# SCH_Control_2024-03-25.net
KiCad netlist of a schematic drawn in EasyEDA
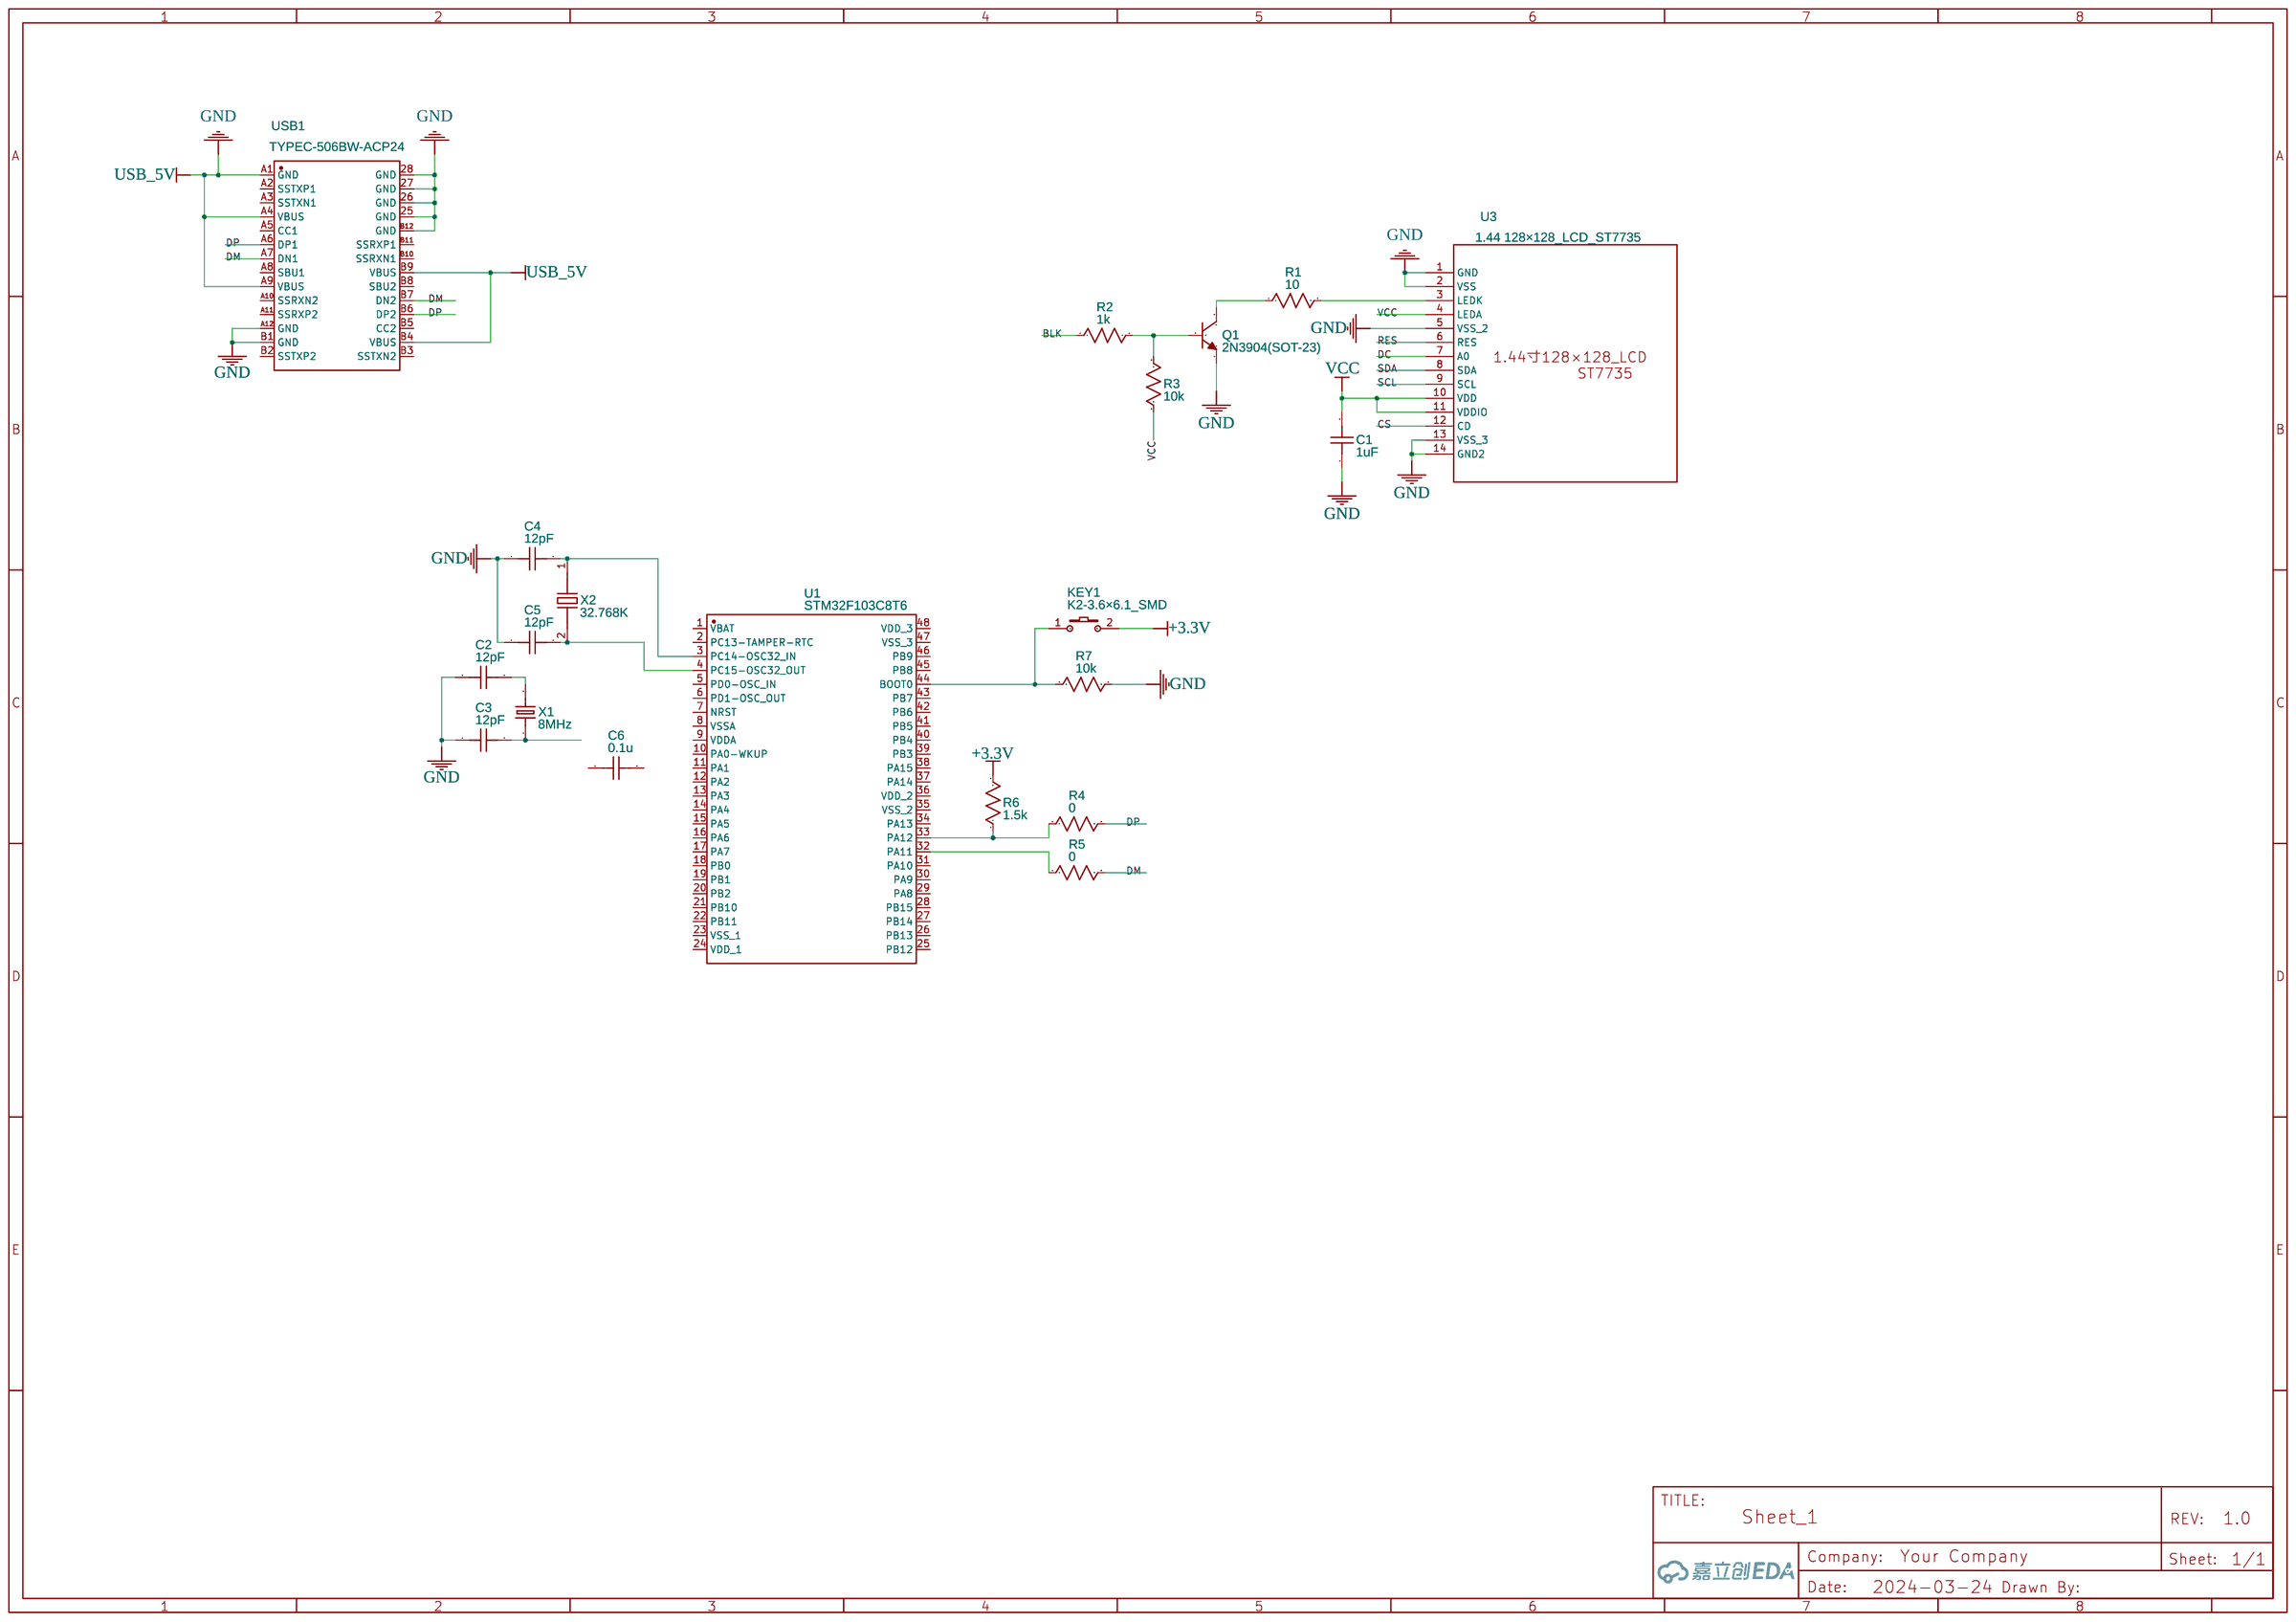
[diagram p0: schematic sheet]

(export (version "E")
  (design (tool "Eeschema 10.0.6"))
  (components
    (comp (ref "C1") (value "1uF") (libsource (lib "") (part "C_0603_US_1")))
    (comp (ref "C2") (value "12pF") (libsource (lib "") (part "C_0603_US")))
    (comp (ref "C3") (value "12pF") (libsource (lib "") (part "C_0603_US")))
    (comp (ref "C4") (value "12pF") (libsource (lib "") (part "C_0603_US")))
    (comp (ref "C5") (value "12pF") (libsource (lib "") (part "C_0603_US")))
    (comp (ref "C6") (value "0.1u") (libsource (lib "") (part "C_0603_US")))
    (comp (ref "KEY1")
      (value "K2-3.6×6.1_SMD")
      (fields (field (name "Manufacturer Part") "K2-1107ST-A4SW-06"))
      (libsource (lib "") (part "K2-3.6×6.1_SMD"))
    )
    (comp (ref "Q1")
      (value "2N3904(SOT-23)")
      (fields (field (name "Manufacturer Part") "2n3904S-RTK/PS") (field (name "Manufacturer") "KEC"))
      (libsource (lib "") (part "2N3904(SOT-23)"))
    )
    (comp (ref "R1") (value "10") (libsource (lib "") (part "R_0603_US")))
    (comp (ref "R2") (value "1k") (libsource (lib "") (part "R_0603_US")))
    (comp (ref "R3") (value "10k") (libsource (lib "") (part "R_0603_US_1")))
    (comp (ref "R4") (value "0") (libsource (lib "") (part "R_0603_US")))
    (comp (ref "R5") (value "0") (libsource (lib "") (part "R_0603_US")))
    (comp (ref "R6") (value "1.5k") (libsource (lib "") (part "R_0603_US_1")))
    (comp (ref "R7") (value "10k") (libsource (lib "") (part "R_0603_US")))
    (comp (ref "U1")
      (value "STM32F103C8T6")
      (fields (field (name "Manufacturer") "ST(意法半导体)"))
      (libsource (lib "") (part "STM32F103C8T6"))
    )
    (comp (ref "U3")
      (value "1.44 128×128_LCD_ST7735")
      (libsource (lib "") (part "1.44 128×128_LCD_ST7735【华迪短】"))
    )
    (comp (ref "USB1")
      (value "TYPEC-506BW-ACP24")
      (fields (field (name "Manufacturer") "XUNPU(讯普)"))
      (libsource (lib "") (part "TYPEC-506BW-ACP24"))
    )
    (comp (ref "X1")
      (value "8MHz")
      (fields
        (field (name "Manufacturer Part") "XJHCELNANF-8M")
        (field (name "Manufacturer") "TAITIEN(泰艺电子)")
      )
      (libsource (lib "") (part "XJHCCLNAND-8M"))
    )
    (comp (ref "X2")
      (value "32.768K")
      (fields (field (name "Manufacturer Part") "贴片晶振32.768k"))
      (libsource (lib "") (part "贴片晶振32.768K"))
    )
  )
  (nets
    (net (code "1") (name "+3.3V") (class "Default")
      (node (ref "KEY1") (pin "2") (pinfunction "2_2") (pintype "unspecified"))
      (node (ref "R6") (pin "2") (pinfunction "2_2") (pintype "unspecified"))
    )
    (net (code "2") (name "/BLK") (class "Default")
      (node (ref "R2") (pin "1") (pinfunction "1_1") (pintype "unspecified"))
    )
    (net (code "3") (name "/CS") (class "Default")
      (node (ref "U3") (pin "12") (pinfunction "CD_12") (pintype "unspecified"))
    )
    (net (code "4") (name "/DC") (class "Default")
      (node (ref "U3") (pin "7") (pinfunction "A0_7") (pintype "unspecified"))
    )
    (net (code "5") (name "/DM") (class "Default")
      (node (ref "R5") (pin "2") (pinfunction "2_2") (pintype "unspecified"))
      (node (ref "USB1") (pin "A7") (pinfunction "DN1_A7") (pintype "unspecified"))
      (node (ref "USB1") (pin "B7") (pinfunction "DN2_B7") (pintype "unspecified"))
    )
    (net (code "6") (name "/DP") (class "Default")
      (node (ref "R4") (pin "2") (pinfunction "2_2") (pintype "unspecified"))
      (node (ref "USB1") (pin "A6") (pinfunction "DP1_A6") (pintype "unspecified"))
      (node (ref "USB1") (pin "B6") (pinfunction "DP2_B6") (pintype "unspecified"))
    )
    (net (code "7") (name "/RES") (class "Default")
      (node (ref "U3") (pin "6") (pinfunction "RES_6") (pintype "unspecified"))
    )
    (net (code "8") (name "/SCL") (class "Default")
      (node (ref "U3") (pin "9") (pinfunction "SCL_9") (pintype "unspecified"))
    )
    (net (code "9") (name "/SDA") (class "Default")
      (node (ref "U3") (pin "8") (pinfunction "SDA_8") (pintype "unspecified"))
    )
    (net (code "10") (name "GND") (class "Default")
      (node (ref "C1") (pin "1") (pinfunction "1_1") (pintype "unspecified"))
      (node (ref "C2") (pin "1") (pinfunction "1_1") (pintype "unspecified"))
      (node (ref "C3") (pin "1") (pinfunction "1_1") (pintype "unspecified"))
      (node (ref "C4") (pin "1") (pinfunction "1_1") (pintype "unspecified"))
      (node (ref "C5") (pin "1") (pinfunction "1_1") (pintype "unspecified"))
      (node (ref "Q1") (pin "1") (pinfunction "E_1") (pintype "input"))
      (node (ref "R7") (pin "2") (pinfunction "2_2") (pintype "unspecified"))
      (node (ref "U3") (pin "1") (pinfunction "GND_1") (pintype "unspecified"))
      (node (ref "U3") (pin "13") (pinfunction "VSS_3_13") (pintype "unspecified"))
      (node (ref "U3") (pin "14") (pinfunction "GND2_14") (pintype "unspecified"))
      (node (ref "U3") (pin "2") (pinfunction "VSS_2") (pintype "unspecified"))
      (node (ref "U3") (pin "5") (pinfunction "VSS_2_5") (pintype "unspecified"))
      (node (ref "USB1") (pin "25") (pinfunction "GND_25") (pintype "unspecified"))
      (node (ref "USB1") (pin "26") (pinfunction "GND_26") (pintype "unspecified"))
      (node (ref "USB1") (pin "27") (pinfunction "GND_27") (pintype "unspecified"))
      (node (ref "USB1") (pin "28") (pinfunction "GND_28") (pintype "unspecified"))
      (node (ref "USB1") (pin "A1") (pinfunction "GND_A1") (pintype "unspecified"))
      (node (ref "USB1") (pin "A12") (pinfunction "GND_A12") (pintype "unspecified"))
      (node (ref "USB1") (pin "A4") (pinfunction "VBUS_A4") (pintype "unspecified"))
      (node (ref "USB1") (pin "A9") (pinfunction "VBUS_A9") (pintype "unspecified"))
      (node (ref "USB1") (pin "B1") (pinfunction "GND_B1") (pintype "unspecified"))
      (node (ref "USB1") (pin "B12") (pinfunction "GND_B12") (pintype "unspecified"))
      (node (ref "USB1") (pin "B4") (pinfunction "VBUS_B4") (pintype "unspecified"))
      (node (ref "USB1") (pin "B9") (pinfunction "VBUS_B9") (pintype "unspecified"))
    )
    (net (code "11") (name "Net-(C2-Pad2)") (class "Default")
      (node (ref "C2") (pin "2") (pinfunction "2_2") (pintype "unspecified"))
      (node (ref "X1") (pin "2") (pinfunction "2_2") (pintype "unspecified"))
    )
    (net (code "12") (name "Net-(C3-Pad2)") (class "Default")
      (node (ref "C3") (pin "2") (pinfunction "2_2") (pintype "unspecified"))
      (node (ref "X1") (pin "1") (pinfunction "1_1") (pintype "unspecified"))
    )
    (net (code "13") (name "Net-(Q1-B)") (class "Default")
      (node (ref "Q1") (pin "2") (pinfunction "B_2") (pintype "input"))
      (node (ref "R2") (pin "2") (pinfunction "2_2") (pintype "unspecified"))
      (node (ref "R3") (pin "2") (pinfunction "2_2") (pintype "unspecified"))
    )
    (net (code "14") (name "Net-(Q1-C)") (class "Default")
      (node (ref "Q1") (pin "3") (pinfunction "C_3") (pintype "input"))
      (node (ref "R1") (pin "1") (pinfunction "1_1") (pintype "unspecified"))
    )
    (net (code "15") (name "Net-(U1-BOOT0)") (class "Default")
      (node (ref "KEY1") (pin "1") (pinfunction "1_1") (pintype "unspecified"))
      (node (ref "R7") (pin "1") (pinfunction "1_1") (pintype "unspecified"))
      (node (ref "U1") (pin "44") (pinfunction "BOOT0_44") (pintype "unspecified"))
    )
    (net (code "16") (name "Net-(U1-PA11)") (class "Default")
      (node (ref "R5") (pin "1") (pinfunction "1_1") (pintype "unspecified"))
      (node (ref "U1") (pin "32") (pinfunction "PA11_32") (pintype "unspecified"))
    )
    (net (code "17") (name "Net-(U1-PA12)") (class "Default")
      (node (ref "R4") (pin "1") (pinfunction "1_1") (pintype "unspecified"))
      (node (ref "R6") (pin "1") (pinfunction "1_1") (pintype "unspecified"))
      (node (ref "U1") (pin "33") (pinfunction "PA12_33") (pintype "unspecified"))
    )
    (net (code "18") (name "Net-(U1-PC14-OSC32_IN)") (class "Default")
      (node (ref "C4") (pin "2") (pinfunction "2_2") (pintype "unspecified"))
      (node (ref "U1") (pin "3") (pinfunction "PC14-OSC32_IN_3") (pintype "unspecified"))
      (node (ref "X2") (pin "1") (pinfunction "1_1") (pintype "input"))
    )
    (net (code "19") (name "Net-(U1-PC15-OSC32_OUT)") (class "Default")
      (node (ref "C5") (pin "2") (pinfunction "2_2") (pintype "unspecified"))
      (node (ref "U1") (pin "4") (pinfunction "PC15-OSC32_OUT_4") (pintype "unspecified"))
      (node (ref "X2") (pin "2") (pinfunction "2_2") (pintype "input"))
    )
    (net (code "20") (name "Net-(U3-LEDK)") (class "Default")
      (node (ref "R1") (pin "2") (pinfunction "2_2") (pintype "unspecified"))
      (node (ref "U3") (pin "3") (pinfunction "LEDK_3") (pintype "unspecified"))
    )
    (net (code "21") (name "VCC") (class "Default")
      (node (ref "C1") (pin "2") (pinfunction "2_2") (pintype "unspecified"))
      (node (ref "R3") (pin "1") (pinfunction "1_1") (pintype "unspecified"))
      (node (ref "U3") (pin "10") (pinfunction "VDD_10") (pintype "unspecified"))
      (node (ref "U3") (pin "11") (pinfunction "VDDIO_11") (pintype "unspecified"))
      (node (ref "U3") (pin "4") (pinfunction "LEDA_4") (pintype "unspecified"))
    )
    (net (code "22") (name "unconnected-(C6-Pad1)") (class "Default")
      (node (ref "C6") (pin "1") (pinfunction "1_1") (pintype "unspecified"))
    )
    (net (code "23") (name "unconnected-(C6-Pad2)") (class "Default")
      (node (ref "C6") (pin "2") (pinfunction "2_2") (pintype "unspecified"))
    )
    (net (code "24") (name "unconnected-(U1-NRST-Pad7)") (class "Default")
      (node (ref "U1") (pin "7") (pinfunction "NRST_7") (pintype "unspecified"))
    )
    (net (code "25") (name "unconnected-(U1-PA0-WKUP-Pad10)") (class "Default")
      (node (ref "U1") (pin "10") (pinfunction "PA0-WKUP_10") (pintype "unspecified"))
    )
    (net (code "26") (name "unconnected-(U1-PA1-Pad11)") (class "Default")
      (node (ref "U1") (pin "11") (pinfunction "PA1_11") (pintype "unspecified"))
    )
    (net (code "27") (name "unconnected-(U1-PA2-Pad12)") (class "Default")
      (node (ref "U1") (pin "12") (pinfunction "PA2_12") (pintype "unspecified"))
    )
    (net (code "28") (name "unconnected-(U1-PA3-Pad13)") (class "Default")
      (node (ref "U1") (pin "13") (pinfunction "PA3_13") (pintype "unspecified"))
    )
    (net (code "29") (name "unconnected-(U1-PA4-Pad14)") (class "Default")
      (node (ref "U1") (pin "14") (pinfunction "PA4_14") (pintype "unspecified"))
    )
    (net (code "30") (name "unconnected-(U1-PA5-Pad15)") (class "Default")
      (node (ref "U1") (pin "15") (pinfunction "PA5_15") (pintype "unspecified"))
    )
    (net (code "31") (name "unconnected-(U1-PA6-Pad16)") (class "Default")
      (node (ref "U1") (pin "16") (pinfunction "PA6_16") (pintype "unspecified"))
    )
    (net (code "32") (name "unconnected-(U1-PA7-Pad17)") (class "Default")
      (node (ref "U1") (pin "17") (pinfunction "PA7_17") (pintype "unspecified"))
    )
    (net (code "33") (name "unconnected-(U1-PA8-Pad29)") (class "Default")
      (node (ref "U1") (pin "29") (pinfunction "PA8_29") (pintype "unspecified"))
    )
    (net (code "34") (name "unconnected-(U1-PA9-Pad30)") (class "Default")
      (node (ref "U1") (pin "30") (pinfunction "PA9_30") (pintype "unspecified"))
    )
    (net (code "35") (name "unconnected-(U1-PA10-Pad31)") (class "Default")
      (node (ref "U1") (pin "31") (pinfunction "PA10_31") (pintype "unspecified"))
    )
    (net (code "36") (name "unconnected-(U1-PA13-Pad34)") (class "Default")
      (node (ref "U1") (pin "34") (pinfunction "PA13_34") (pintype "unspecified"))
    )
    (net (code "37") (name "unconnected-(U1-PA14-Pad37)") (class "Default")
      (node (ref "U1") (pin "37") (pinfunction "PA14_37") (pintype "unspecified"))
    )
    (net (code "38") (name "unconnected-(U1-PA15-Pad38)") (class "Default")
      (node (ref "U1") (pin "38") (pinfunction "PA15_38") (pintype "unspecified"))
    )
    (net (code "39") (name "unconnected-(U1-PB0-Pad18)") (class "Default")
      (node (ref "U1") (pin "18") (pinfunction "PB0_18") (pintype "unspecified"))
    )
    (net (code "40") (name "unconnected-(U1-PB1-Pad19)") (class "Default")
      (node (ref "U1") (pin "19") (pinfunction "PB1_19") (pintype "unspecified"))
    )
    (net (code "41") (name "unconnected-(U1-PB2-Pad20)") (class "Default")
      (node (ref "U1") (pin "20") (pinfunction "PB2_20") (pintype "unspecified"))
    )
    (net (code "42") (name "unconnected-(U1-PB3-Pad39)") (class "Default")
      (node (ref "U1") (pin "39") (pinfunction "PB3_39") (pintype "unspecified"))
    )
    (net (code "43") (name "unconnected-(U1-PB4-Pad40)") (class "Default")
      (node (ref "U1") (pin "40") (pinfunction "PB4_40") (pintype "unspecified"))
    )
    (net (code "44") (name "unconnected-(U1-PB5-Pad41)") (class "Default")
      (node (ref "U1") (pin "41") (pinfunction "PB5_41") (pintype "unspecified"))
    )
    (net (code "45") (name "unconnected-(U1-PB6-Pad42)") (class "Default")
      (node (ref "U1") (pin "42") (pinfunction "PB6_42") (pintype "unspecified"))
    )
    (net (code "46") (name "unconnected-(U1-PB7-Pad43)") (class "Default")
      (node (ref "U1") (pin "43") (pinfunction "PB7_43") (pintype "unspecified"))
    )
    (net (code "47") (name "unconnected-(U1-PB8-Pad45)") (class "Default")
      (node (ref "U1") (pin "45") (pinfunction "PB8_45") (pintype "unspecified"))
    )
    (net (code "48") (name "unconnected-(U1-PB9-Pad46)") (class "Default")
      (node (ref "U1") (pin "46") (pinfunction "PB9_46") (pintype "unspecified"))
    )
    (net (code "49") (name "unconnected-(U1-PB10-Pad21)") (class "Default")
      (node (ref "U1") (pin "21") (pinfunction "PB10_21") (pintype "unspecified"))
    )
    (net (code "50") (name "unconnected-(U1-PB11-Pad22)") (class "Default")
      (node (ref "U1") (pin "22") (pinfunction "PB11_22") (pintype "unspecified"))
    )
    (net (code "51") (name "unconnected-(U1-PB12-Pad25)") (class "Default")
      (node (ref "U1") (pin "25") (pinfunction "PB12_25") (pintype "unspecified"))
    )
    (net (code "52") (name "unconnected-(U1-PB13-Pad26)") (class "Default")
      (node (ref "U1") (pin "26") (pinfunction "PB13_26") (pintype "unspecified"))
    )
    (net (code "53") (name "unconnected-(U1-PB14-Pad27)") (class "Default")
      (node (ref "U1") (pin "27") (pinfunction "PB14_27") (pintype "unspecified"))
    )
    (net (code "54") (name "unconnected-(U1-PB15-Pad28)") (class "Default")
      (node (ref "U1") (pin "28") (pinfunction "PB15_28") (pintype "unspecified"))
    )
    (net (code "55") (name "unconnected-(U1-PC13-TAMPER-RTC-Pad2)") (class "Default")
      (node (ref "U1") (pin "2") (pinfunction "PC13-TAMPER-RTC_2") (pintype "unspecified"))
    )
    (net (code "56") (name "unconnected-(U1-PD0-OSC_IN-Pad5)") (class "Default")
      (node (ref "U1") (pin "5") (pinfunction "PD0-OSC_IN_5") (pintype "unspecified"))
    )
    (net (code "57") (name "unconnected-(U1-PD1-OSC_OUT-Pad6)") (class "Default")
      (node (ref "U1") (pin "6") (pinfunction "PD1-OSC_OUT_6") (pintype "unspecified"))
    )
    (net (code "58") (name "unconnected-(U1-VBAT-Pad1)") (class "Default")
      (node (ref "U1") (pin "1") (pinfunction "VBAT_1") (pintype "unspecified"))
    )
    (net (code "59") (name "unconnected-(U1-VDDA-Pad9)") (class "Default")
      (node (ref "U1") (pin "9") (pinfunction "VDDA_9") (pintype "unspecified"))
    )
    (net (code "60") (name "unconnected-(U1-VDD_1-Pad24)") (class "Default")
      (node (ref "U1") (pin "24") (pinfunction "VDD_1_24") (pintype "unspecified"))
    )
    (net (code "61") (name "unconnected-(U1-VDD_2-Pad36)") (class "Default")
      (node (ref "U1") (pin "36") (pinfunction "VDD_2_36") (pintype "unspecified"))
    )
    (net (code "62") (name "unconnected-(U1-VDD_3-Pad48)") (class "Default")
      (node (ref "U1") (pin "48") (pinfunction "VDD_3_48") (pintype "unspecified"))
    )
    (net (code "63") (name "unconnected-(U1-VSSA-Pad8)") (class "Default")
      (node (ref "U1") (pin "8") (pinfunction "VSSA_8") (pintype "unspecified"))
    )
    (net (code "64") (name "unconnected-(U1-VSS_1-Pad23)") (class "Default")
      (node (ref "U1") (pin "23") (pinfunction "VSS_1_23") (pintype "unspecified"))
    )
    (net (code "65") (name "unconnected-(U1-VSS_2-Pad35)") (class "Default")
      (node (ref "U1") (pin "35") (pinfunction "VSS_2_35") (pintype "unspecified"))
    )
    (net (code "66") (name "unconnected-(U1-VSS_3-Pad47)") (class "Default")
      (node (ref "U1") (pin "47") (pinfunction "VSS_3_47") (pintype "unspecified"))
    )
    (net (code "67") (name "unconnected-(USB1-CC1-PadA5)") (class "Default")
      (node (ref "USB1") (pin "A5") (pinfunction "CC1_A5") (pintype "unspecified"))
    )
    (net (code "68") (name "unconnected-(USB1-CC2-PadB5)") (class "Default")
      (node (ref "USB1") (pin "B5") (pinfunction "CC2_B5") (pintype "unspecified"))
    )
    (net (code "69") (name "unconnected-(USB1-SBU1-PadA8)") (class "Default")
      (node (ref "USB1") (pin "A8") (pinfunction "SBU1_A8") (pintype "unspecified"))
    )
    (net (code "70") (name "unconnected-(USB1-SBU2-PadB8)") (class "Default")
      (node (ref "USB1") (pin "B8") (pinfunction "SBU2_B8") (pintype "unspecified"))
    )
    (net (code "71") (name "unconnected-(USB1-SSRXN1-PadB10)") (class "Default")
      (node (ref "USB1") (pin "B10") (pinfunction "SSRXN1_B10") (pintype "unspecified"))
    )
    (net (code "72") (name "unconnected-(USB1-SSRXN2-PadA10)") (class "Default")
      (node (ref "USB1") (pin "A10") (pinfunction "SSRXN2_A10") (pintype "unspecified"))
    )
    (net (code "73") (name "unconnected-(USB1-SSRXP1-PadB11)") (class "Default")
      (node (ref "USB1") (pin "B11") (pinfunction "SSRXP1_B11") (pintype "unspecified"))
    )
    (net (code "74") (name "unconnected-(USB1-SSRXP2-PadA11)") (class "Default")
      (node (ref "USB1") (pin "A11") (pinfunction "SSRXP2_A11") (pintype "unspecified"))
    )
    (net (code "75") (name "unconnected-(USB1-SSTXN1-PadA3)") (class "Default")
      (node (ref "USB1") (pin "A3") (pinfunction "SSTXN1_A3") (pintype "unspecified"))
    )
    (net (code "76") (name "unconnected-(USB1-SSTXN2-PadB3)") (class "Default")
      (node (ref "USB1") (pin "B3") (pinfunction "SSTXN2_B3") (pintype "unspecified"))
    )
    (net (code "77") (name "unconnected-(USB1-SSTXP1-PadA2)") (class "Default")
      (node (ref "USB1") (pin "A2") (pinfunction "SSTXP1_A2") (pintype "unspecified"))
    )
    (net (code "78") (name "unconnected-(USB1-SSTXP2-PadB2)") (class "Default")
      (node (ref "USB1") (pin "B2") (pinfunction "SSTXP2_B2") (pintype "unspecified"))
    )
  )
)
